# TTP224.net
KiCad netlist of a schematic drawn in Altium Designer
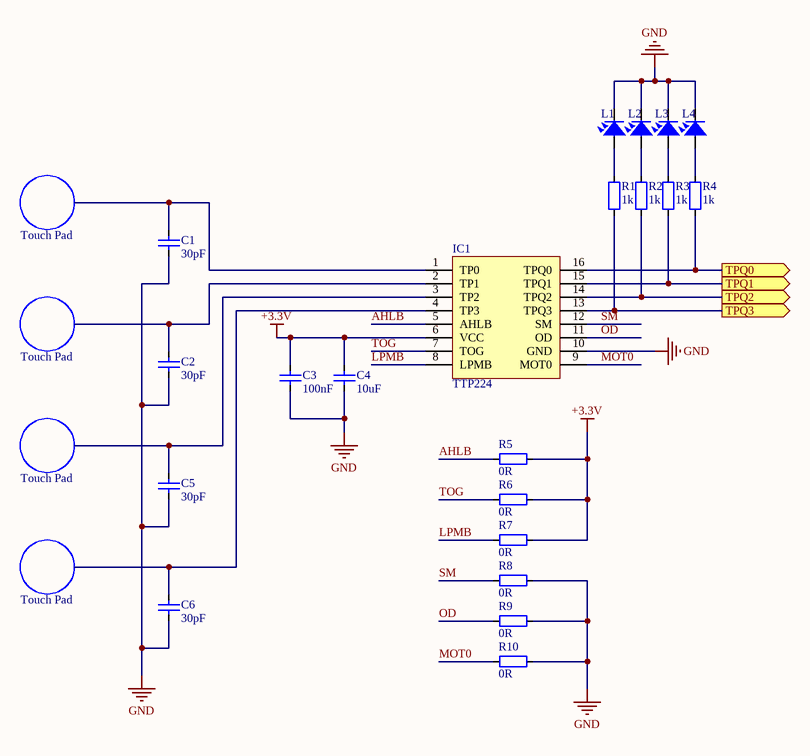
[diagram p0: TTP224.SchDoc]

(export (version "E")
  (design (tool "Eeschema 10.0.6"))
  (components
    (comp (ref "C1")
      (value "30pF")
      (footprint "CAP_0805")
      (description "Capacitor")
      (fields (field (name "PUBLISHER") "Altium Limited"))
      (libsource (lib "My Library") (part "CapSMD"))
    )
    (comp (ref "C2")
      (value "30pF")
      (footprint "CAP_0805")
      (description "Capacitor")
      (fields (field (name "PUBLISHER") "Altium Limited"))
      (libsource (lib "My Library") (part "CapSMD"))
    )
    (comp (ref "C3")
      (value "100nF")
      (footprint "CAP_0805")
      (description "Capacitor")
      (fields (field (name "PUBLISHER") "Altium Limited"))
      (libsource (lib "My Library") (part "CapSMD"))
    )
    (comp (ref "C4")
      (value "10uF")
      (footprint "CAP_0805")
      (description "Capacitor")
      (fields (field (name "PUBLISHER") "Altium Limited"))
      (libsource (lib "My Library") (part "CapSMD"))
    )
    (comp (ref "C5")
      (value "30pF")
      (footprint "CAP_0805")
      (description "Capacitor")
      (fields (field (name "PUBLISHER") "Altium Limited"))
      (libsource (lib "My Library") (part "CapSMD"))
    )
    (comp (ref "C6")
      (value "30pF")
      (footprint "CAP_0805")
      (description "Capacitor")
      (fields (field (name "PUBLISHER") "Altium Limited"))
      (libsource (lib "My Library") (part "CapSMD"))
    )
    (comp (ref "IC1") (value "TTP224") (footprint "TTP224") (libsource (lib "My Library") (part "TTP224")))
    (comp (ref "L1")
      (value "LED")
      (footprint "LED-0805-Red")
      (description "LED Single colour Green and Red")
      (libsource (lib "My Library") (part "LED"))
    )
    (comp (ref "L2")
      (value "LED")
      (footprint "LED-0805-Red")
      (description "LED Single colour Green and Red")
      (libsource (lib "My Library") (part "LED"))
    )
    (comp (ref "L3")
      (value "LED")
      (footprint "LED-0805-Red")
      (description "LED Single colour Green and Red")
      (libsource (lib "My Library") (part "LED"))
    )
    (comp (ref "L4")
      (value "LED")
      (footprint "LED-0805-Red")
      (description "LED Single colour Green and Red")
      (libsource (lib "My Library") (part "LED"))
    )
    (comp (ref "R1")
      (value "1k")
      (footprint "RES-SMD-0805")
      (description "Resistor")
      (fields
        (field (name "MANUFACTURER") "Generic Components")
        (field (name "PUBLISHER") "Altium Hobart Technology Centre")
      )
      (libsource (lib "My Library") (part "Resistor - SMD"))
    )
    (comp (ref "R2")
      (value "1k")
      (footprint "RES-SMD-0805")
      (description "Resistor")
      (fields
        (field (name "MANUFACTURER") "Generic Components")
        (field (name "PUBLISHER") "Altium Hobart Technology Centre")
      )
      (libsource (lib "My Library") (part "Resistor - SMD"))
    )
    (comp (ref "R3")
      (value "1k")
      (footprint "RES-SMD-0805")
      (description "Resistor")
      (fields
        (field (name "MANUFACTURER") "Generic Components")
        (field (name "PUBLISHER") "Altium Hobart Technology Centre")
      )
      (libsource (lib "My Library") (part "Resistor - SMD"))
    )
    (comp (ref "R4")
      (value "1k")
      (footprint "RES-SMD-0805")
      (description "Resistor")
      (fields
        (field (name "MANUFACTURER") "Generic Components")
        (field (name "PUBLISHER") "Altium Hobart Technology Centre")
      )
      (libsource (lib "My Library") (part "Resistor - SMD"))
    )
    (comp (ref "R5")
      (value "0R")
      (footprint "RES-SMD-0805")
      (description "Resistor")
      (fields
        (field (name "MANUFACTURER") "Generic Components")
        (field (name "PUBLISHER") "Altium Hobart Technology Centre")
      )
      (libsource (lib "My Library") (part "Resistor - SMD"))
    )
    (comp (ref "R6")
      (value "0R")
      (footprint "RES-SMD-0805")
      (description "Resistor")
      (fields
        (field (name "MANUFACTURER") "Generic Components")
        (field (name "PUBLISHER") "Altium Hobart Technology Centre")
      )
      (libsource (lib "My Library") (part "Resistor - SMD"))
    )
    (comp (ref "R7")
      (value "0R")
      (footprint "RES-SMD-0805")
      (description "Resistor")
      (fields
        (field (name "MANUFACTURER") "Generic Components")
        (field (name "PUBLISHER") "Altium Hobart Technology Centre")
      )
      (libsource (lib "My Library") (part "Resistor - SMD"))
    )
    (comp (ref "R8")
      (value "0R")
      (footprint "RES-SMD-0805")
      (description "Resistor")
      (fields
        (field (name "MANUFACTURER") "Generic Components")
        (field (name "PUBLISHER") "Altium Hobart Technology Centre")
      )
      (libsource (lib "My Library") (part "Resistor - SMD"))
    )
    (comp (ref "R9")
      (value "0R")
      (footprint "RES-SMD-0805")
      (description "Resistor")
      (fields
        (field (name "MANUFACTURER") "Generic Components")
        (field (name "PUBLISHER") "Altium Hobart Technology Centre")
      )
      (libsource (lib "My Library") (part "Resistor - SMD"))
    )
    (comp (ref "R10")
      (value "0R")
      (footprint "RES-SMD-0805")
      (description "Resistor")
      (fields
        (field (name "MANUFACTURER") "Generic Components")
        (field (name "PUBLISHER") "Altium Hobart Technology Centre")
      )
      (libsource (lib "My Library") (part "Resistor - SMD"))
    )
  )
  (nets
    (net (code "1") (name "+3.3V") (class "Default")
      (node (ref "C3") (pin "2") (pinfunction "2_2") (pintype "passive"))
      (node (ref "C4") (pin "2") (pinfunction "2_2") (pintype "passive"))
      (node (ref "IC1") (pin "6") (pinfunction "VCC_6") (pintype "passive"))
      (node (ref "R5") (pin "2") (pinfunction "2_2") (pintype "passive"))
      (node (ref "R6") (pin "2") (pinfunction "2_2") (pintype "passive"))
      (node (ref "R7") (pin "2") (pinfunction "2_2") (pintype "passive"))
    )
    (net (code "2") (name "/AHLB") (class "Default")
      (node (ref "IC1") (pin "5") (pinfunction "AHLB_5") (pintype "passive"))
      (node (ref "R5") (pin "1") (pinfunction "1_1") (pintype "passive"))
    )
    (net (code "3") (name "/LPMB") (class "Default")
      (node (ref "IC1") (pin "8") (pinfunction "LPMB_8") (pintype "passive"))
      (node (ref "R7") (pin "1") (pinfunction "1_1") (pintype "passive"))
    )
    (net (code "4") (name "/MOT0") (class "Default")
      (node (ref "IC1") (pin "9") (pinfunction "MOT0_9") (pintype "passive"))
      (node (ref "R10") (pin "1") (pinfunction "1_1") (pintype "passive"))
    )
    (net (code "5") (name "/OD") (class "Default")
      (node (ref "IC1") (pin "11") (pinfunction "OD_11") (pintype "passive"))
      (node (ref "R9") (pin "1") (pinfunction "1_1") (pintype "passive"))
    )
    (net (code "6") (name "/SM") (class "Default")
      (node (ref "IC1") (pin "12") (pinfunction "SM_12") (pintype "passive"))
      (node (ref "R8") (pin "1") (pinfunction "1_1") (pintype "passive"))
    )
    (net (code "7") (name "/TOG") (class "Default")
      (node (ref "IC1") (pin "7") (pinfunction "TOG_7") (pintype "passive"))
      (node (ref "R6") (pin "1") (pinfunction "1_1") (pintype "passive"))
    )
    (net (code "8") (name "/TPQ0") (class "Default")
      (node (ref "IC1") (pin "16") (pinfunction "TPQ0_16") (pintype "passive"))
      (node (ref "R4") (pin "1") (pinfunction "1_1") (pintype "passive"))
    )
    (net (code "9") (name "/TPQ1") (class "Default")
      (node (ref "IC1") (pin "15") (pinfunction "TPQ1_15") (pintype "passive"))
      (node (ref "R3") (pin "1") (pinfunction "1_1") (pintype "passive"))
    )
    (net (code "10") (name "/TPQ2") (class "Default")
      (node (ref "IC1") (pin "14") (pinfunction "TPQ2_14") (pintype "passive"))
      (node (ref "R2") (pin "1") (pinfunction "1_1") (pintype "passive"))
    )
    (net (code "11") (name "/TPQ3") (class "Default")
      (node (ref "IC1") (pin "13") (pinfunction "TPQ3_13") (pintype "passive"))
      (node (ref "R1") (pin "1") (pinfunction "1_1") (pintype "passive"))
    )
    (net (code "12") (name "GND") (class "Default")
      (node (ref "C1") (pin "1") (pinfunction "1_1") (pintype "passive"))
      (node (ref "C2") (pin "1") (pinfunction "1_1") (pintype "passive"))
      (node (ref "C3") (pin "1") (pinfunction "1_1") (pintype "passive"))
      (node (ref "C4") (pin "1") (pinfunction "1_1") (pintype "passive"))
      (node (ref "C5") (pin "1") (pinfunction "1_1") (pintype "passive"))
      (node (ref "C6") (pin "1") (pinfunction "1_1") (pintype "passive"))
      (node (ref "IC1") (pin "10") (pinfunction "GND_10") (pintype "passive"))
      (node (ref "L1") (pin "2") (pinfunction "2_2") (pintype "passive"))
      (node (ref "L2") (pin "2") (pinfunction "2_2") (pintype "passive"))
      (node (ref "L3") (pin "2") (pinfunction "2_2") (pintype "passive"))
      (node (ref "L4") (pin "2") (pinfunction "2_2") (pintype "passive"))
      (node (ref "R10") (pin "2") (pinfunction "2_2") (pintype "passive"))
      (node (ref "R8") (pin "2") (pinfunction "2_2") (pintype "passive"))
      (node (ref "R9") (pin "2") (pinfunction "2_2") (pintype "passive"))
    )
    (net (code "13") (name "Net-(IC1-TP0)") (class "Default")
      (node (ref "C1") (pin "2") (pinfunction "2_2") (pintype "passive"))
      (node (ref "IC1") (pin "1") (pinfunction "TP0_1") (pintype "passive"))
    )
    (net (code "14") (name "Net-(IC1-TP1)") (class "Default")
      (node (ref "C2") (pin "2") (pinfunction "2_2") (pintype "passive"))
      (node (ref "IC1") (pin "2") (pinfunction "TP1_2") (pintype "passive"))
    )
    (net (code "15") (name "Net-(IC1-TP2)") (class "Default")
      (node (ref "C5") (pin "2") (pinfunction "2_2") (pintype "passive"))
      (node (ref "IC1") (pin "3") (pinfunction "TP2_3") (pintype "passive"))
    )
    (net (code "16") (name "Net-(IC1-TP3)") (class "Default")
      (node (ref "C6") (pin "2") (pinfunction "2_2") (pintype "passive"))
      (node (ref "IC1") (pin "4") (pinfunction "TP3_4") (pintype "passive"))
    )
    (net (code "17") (name "Net-(L1-Pad1)") (class "Default")
      (node (ref "L1") (pin "1") (pinfunction "1_1") (pintype "passive"))
      (node (ref "R1") (pin "2") (pinfunction "2_2") (pintype "passive"))
    )
    (net (code "18") (name "Net-(L2-Pad1)") (class "Default")
      (node (ref "L2") (pin "1") (pinfunction "1_1") (pintype "passive"))
      (node (ref "R2") (pin "2") (pinfunction "2_2") (pintype "passive"))
    )
    (net (code "19") (name "Net-(L3-Pad1)") (class "Default")
      (node (ref "L3") (pin "1") (pinfunction "1_1") (pintype "passive"))
      (node (ref "R3") (pin "2") (pinfunction "2_2") (pintype "passive"))
    )
    (net (code "20") (name "Net-(L4-Pad1)") (class "Default")
      (node (ref "L4") (pin "1") (pinfunction "1_1") (pintype "passive"))
      (node (ref "R4") (pin "2") (pinfunction "2_2") (pintype "passive"))
    )
  )
)
